# SCH_SimpleFOC-StepMini_2024-05-25.net
KiCad netlist of a schematic drawn in EasyEDA
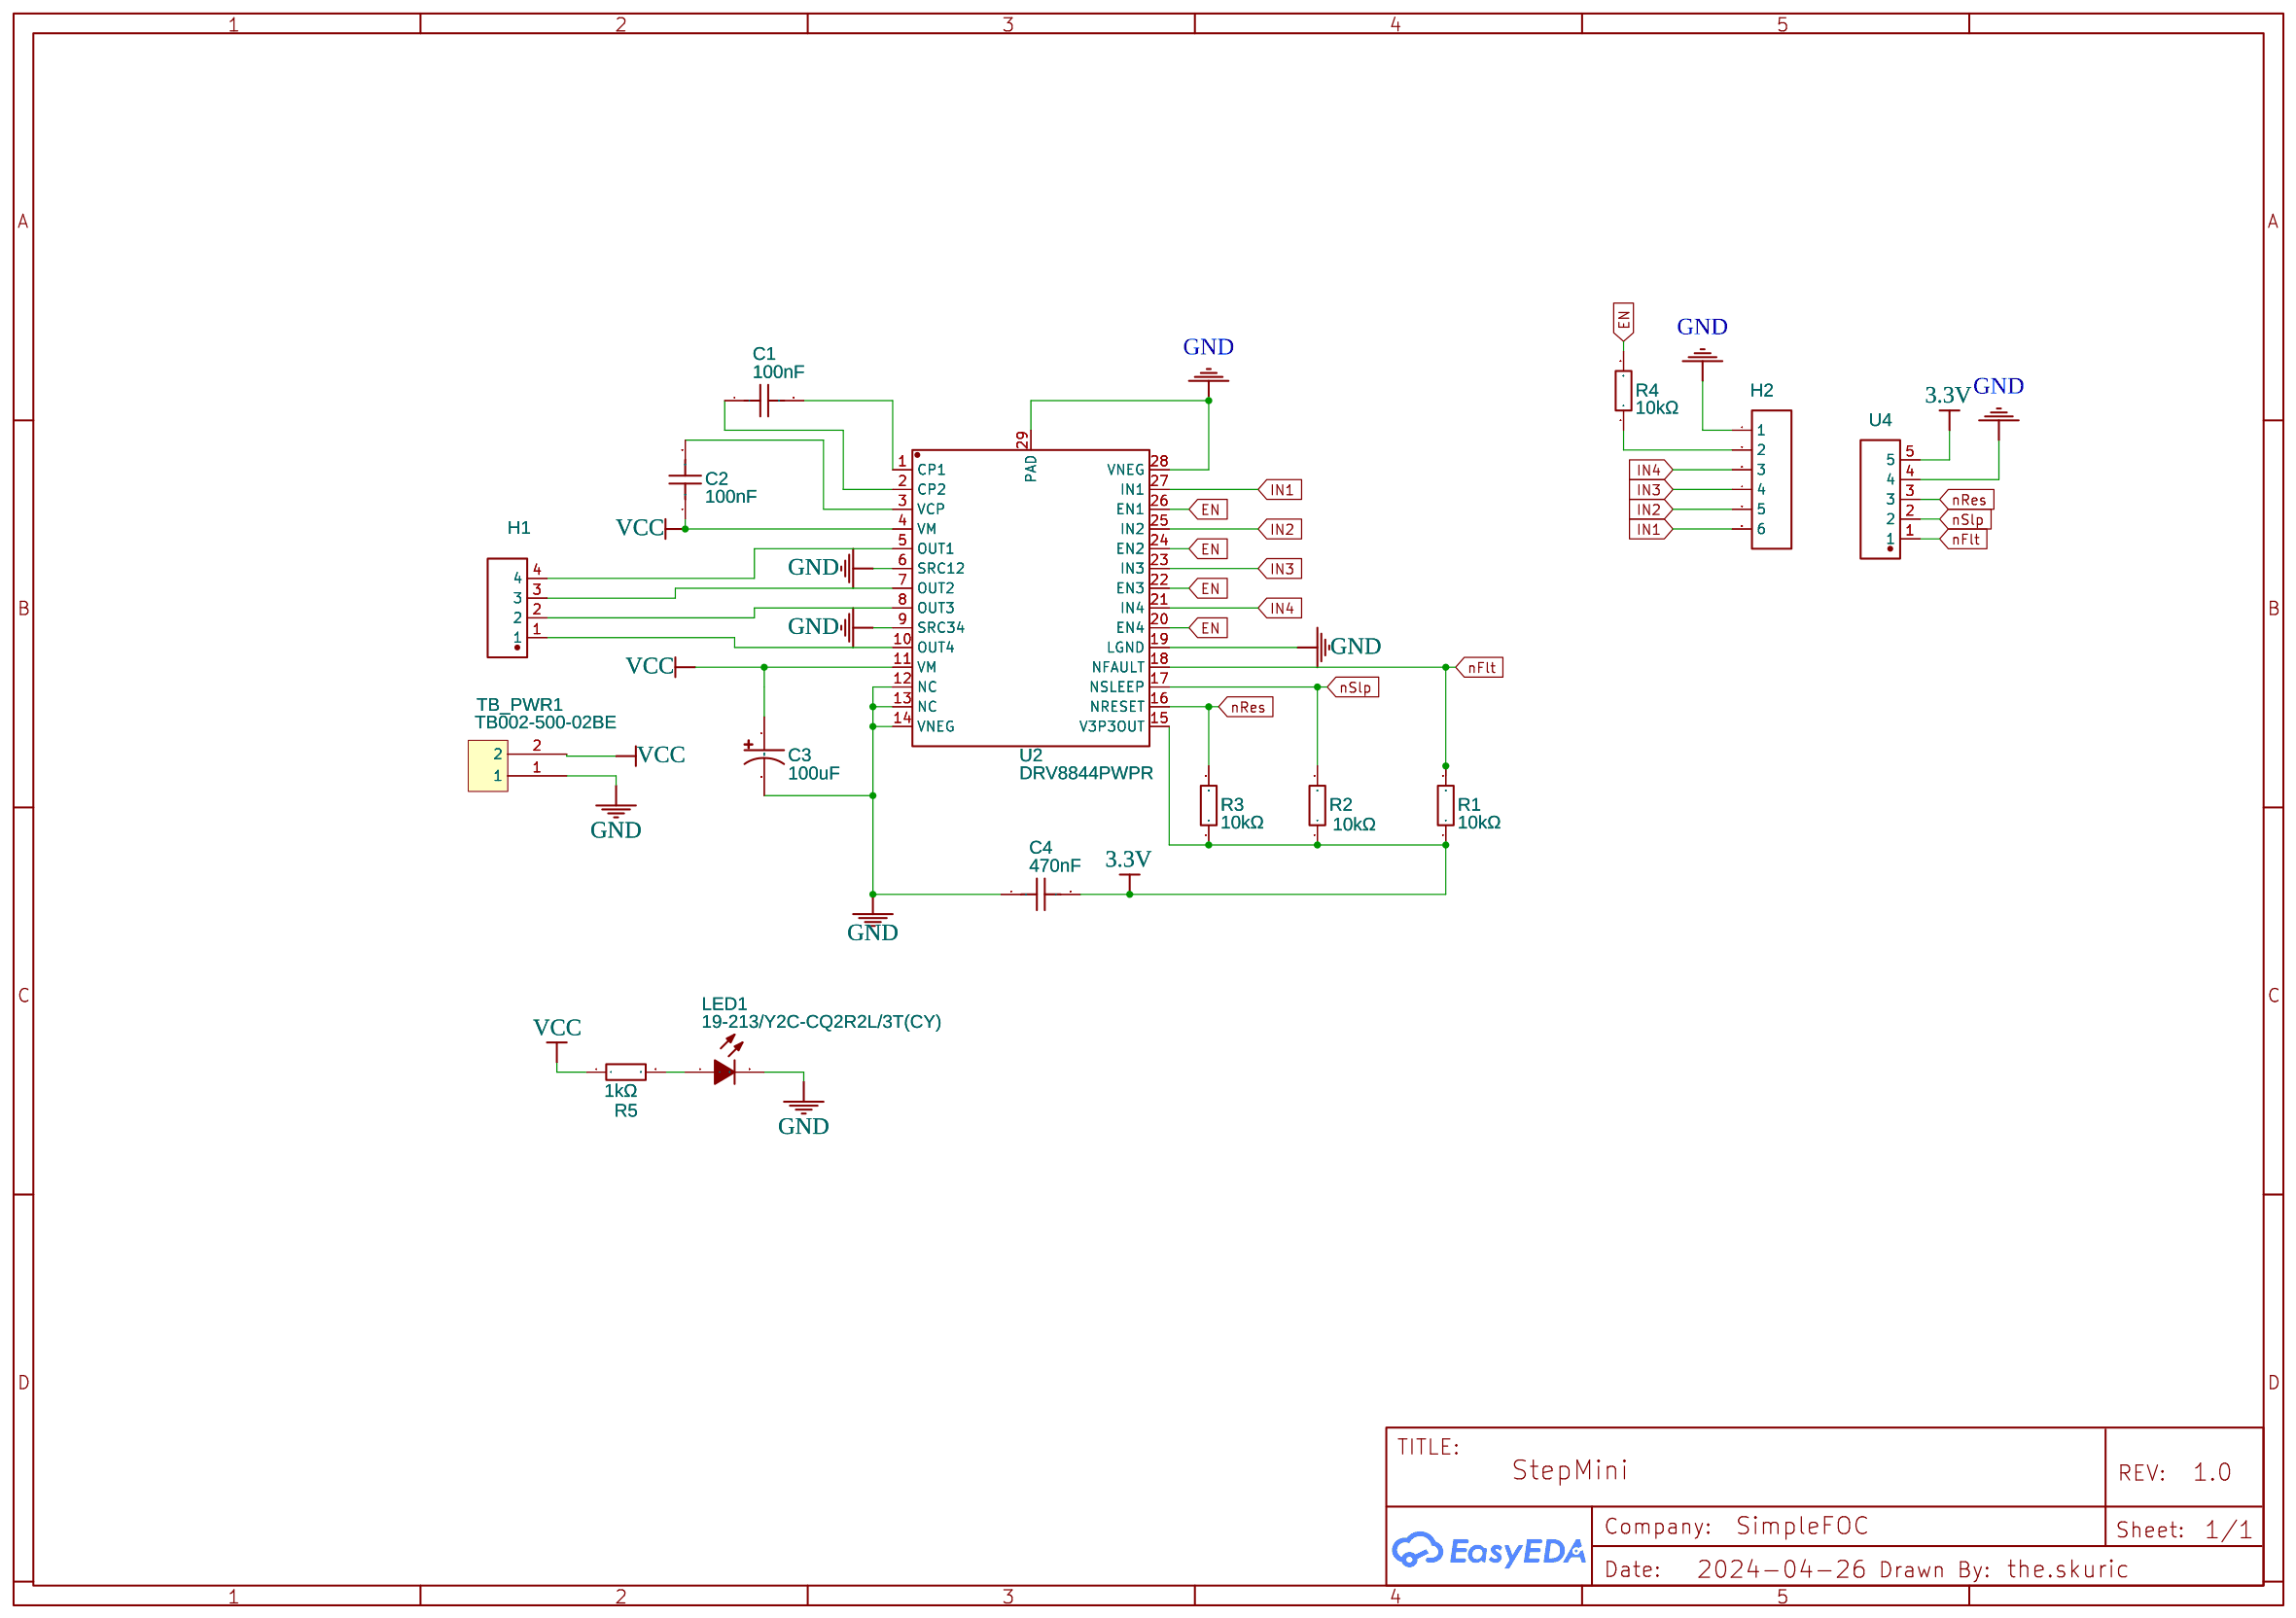
[diagram p0: schematic sheet]

(export (version "E")
  (design (tool "Eeschema 10.0.6"))
  (components
    (comp (ref "C1")
      (value "100nF")
      (fields (field (name "Manufacturer Part") "CL10B104KB8NNNC") (field (name "Manufacturer") "SAMSUNG"))
      (libsource (lib "") (part "CL10B104KB8NNNC_1"))
    )
    (comp (ref "C2")
      (value "100nF")
      (fields (field (name "Manufacturer Part") "CL10B104KB8NNNC") (field (name "Manufacturer") "SAMSUNG"))
      (libsource (lib "") (part "CL10B104KB8NNNC"))
    )
    (comp (ref "C3")
      (value "100uF")
      (fields
        (field (name "Manufacturer Part") "VT1V101M-CRE77")
        (field (name "Manufacturer") "Vertical Technology")
      )
      (libsource (lib "") (part "VT1V101M-CRE77"))
    )
    (comp (ref "C4")
      (value "470nF")
      (fields (field (name "Manufacturer Part") "CC0603ZRY5V6BB474") (field (name "Manufacturer") "YAGEO"))
      (libsource (lib "") (part "CC0603ZRY5V6BB474"))
    )
    (comp (ref "H1")
      (value "KH-2.54PH180-1X4P-L11.5")
      (fields (field (name "Manufacturer") "kinghelm(金航标)"))
      (libsource (lib "") (part "KH-2.54PH180-1X4P-L11.5"))
    )
    (comp (ref "H2")
      (value "Header-Male-2.54_1x6")
      (fields (field (name "Manufacturer Part") "2.54-1x6P直针") (field (name "Manufacturer") "BOOMELE(博穆精密)"))
      (libsource (lib "") (part "Header-Male-2.54_1x6"))
    )
    (comp (ref "LED1")
      (value "19-213/Y2C-CQ2R2L/3T(CY)")
      (fields (field (name "Manufacturer") "EVERLIGHT"))
      (libsource (lib "") (part "19-213/Y2C-CQ2R2L/3T(CY)"))
    )
    (comp (ref "R1")
      (value "10kΩ")
      (fields (field (name "Manufacturer Part") "0603WAF4701T5E") (field (name "Manufacturer") "UniOhm"))
      (libsource (lib "") (part "0603WAF4701T5E"))
    )
    (comp (ref "R2")
      (value "10kΩ")
      (fields (field (name "Manufacturer Part") "0603WAF4701T5E") (field (name "Manufacturer") "UniOhm"))
      (libsource (lib "") (part "0603WAF4701T5E"))
    )
    (comp (ref "R3")
      (value "10kΩ")
      (fields (field (name "Manufacturer Part") "0603WAF4701T5E") (field (name "Manufacturer") "UniOhm"))
      (libsource (lib "") (part "0603WAF4701T5E"))
    )
    (comp (ref "R4")
      (value "10kΩ")
      (fields (field (name "Manufacturer Part") "0603WAF4701T5E") (field (name "Manufacturer") "UniOhm"))
      (libsource (lib "") (part "0603WAF4701T5E"))
    )
    (comp (ref "R5")
      (value "1kΩ")
      (fields (field (name "Manufacturer Part") "0603WAF4701T5E") (field (name "Manufacturer") "UniOhm"))
      (libsource (lib "") (part "0603WAF4701T5E_1"))
    )
    (comp (ref "TB_PWR1") (value "TB002-500-02BE") (libsource (lib "") (part "TB002-500-02BE")))
    (comp (ref "U2")
      (value "DRV8844PWPR")
      (fields (field (name "Manufacturer") "TI(德州仪器)"))
      (libsource (lib "") (part "DRV8844PWPR"))
    )
    (comp (ref "U4")
      (value "KH-2.54FH-1X5P-H8.5")
      (fields (field (name "Manufacturer") "kinghelm(金航标)"))
      (libsource (lib "") (part "KH-2.54FH-1X5P-H8.5"))
    )
  )
  (nets
    (net (code "1") (name "3.3V") (class "Default")
      (node (ref "C4") (pin "2") (pinfunction "2_2") (pintype "unspecified"))
      (node (ref "R1") (pin "1") (pinfunction "1_1") (pintype "input"))
      (node (ref "R2") (pin "1") (pinfunction "1_1") (pintype "input"))
      (node (ref "R3") (pin "1") (pinfunction "1_1") (pintype "input"))
      (node (ref "U2") (pin "15") (pinfunction "V3P3OUT_15") (pintype "unspecified"))
      (node (ref "U4") (pin "5") (pinfunction "5_5") (pintype "unspecified"))
    )
    (net (code "2") (name "EN") (class "Default")
      (node (ref "R4") (pin "2") (pinfunction "2_2") (pintype "input"))
      (node (ref "U2") (pin "20") (pinfunction "EN4_20") (pintype "unspecified"))
      (node (ref "U2") (pin "22") (pinfunction "EN3_22") (pintype "unspecified"))
      (node (ref "U2") (pin "24") (pinfunction "EN2_24") (pintype "unspecified"))
      (node (ref "U2") (pin "26") (pinfunction "EN1_26") (pintype "unspecified"))
    )
    (net (code "3") (name "GND") (class "Default")
      (node (ref "C3") (pin "2") (pinfunction "2_2") (pintype "unspecified"))
      (node (ref "C4") (pin "1") (pinfunction "1_1") (pintype "unspecified"))
      (node (ref "H2") (pin "1") (pinfunction "1_1") (pintype "input"))
      (node (ref "LED1") (pin "2") (pinfunction "C_2") (pintype "input"))
      (node (ref "TB_PWR1") (pin "1") (pinfunction "1_1") (pintype "unspecified"))
      (node (ref "U2") (pin "12") (pinfunction "NC_12") (pintype "unspecified"))
      (node (ref "U2") (pin "13") (pinfunction "NC_13") (pintype "unspecified"))
      (node (ref "U2") (pin "14") (pinfunction "VNEG_14") (pintype "unspecified"))
      (node (ref "U2") (pin "19") (pinfunction "LGND_19") (pintype "unspecified"))
      (node (ref "U2") (pin "28") (pinfunction "VNEG_28") (pintype "unspecified"))
      (node (ref "U2") (pin "29") (pinfunction "PAD_29") (pintype "unspecified"))
      (node (ref "U2") (pin "6") (pinfunction "SRC12_6") (pintype "unspecified"))
      (node (ref "U2") (pin "9") (pinfunction "SRC34_9") (pintype "unspecified"))
      (node (ref "U4") (pin "4") (pinfunction "4_4") (pintype "unspecified"))
    )
    (net (code "4") (name "IN1") (class "Default")
      (node (ref "H2") (pin "6") (pinfunction "6_6") (pintype "input"))
      (node (ref "U2") (pin "27") (pinfunction "IN1_27") (pintype "unspecified"))
    )
    (net (code "5") (name "IN2") (class "Default")
      (node (ref "H2") (pin "5") (pinfunction "5_5") (pintype "input"))
      (node (ref "U2") (pin "25") (pinfunction "IN2_25") (pintype "unspecified"))
    )
    (net (code "6") (name "IN3") (class "Default")
      (node (ref "H2") (pin "4") (pinfunction "4_4") (pintype "input"))
      (node (ref "U2") (pin "23") (pinfunction "IN3_23") (pintype "unspecified"))
    )
    (net (code "7") (name "IN4") (class "Default")
      (node (ref "H2") (pin "3") (pinfunction "3_3") (pintype "input"))
      (node (ref "U2") (pin "21") (pinfunction "IN4_21") (pintype "unspecified"))
    )
    (net (code "8") (name "Net-(H2-Pad2)") (class "Default")
      (node (ref "H2") (pin "2") (pinfunction "2_2") (pintype "input"))
      (node (ref "R4") (pin "1") (pinfunction "1_1") (pintype "input"))
    )
    (net (code "9") (name "Net-(LED1-A)") (class "Default")
      (node (ref "LED1") (pin "1") (pinfunction "A_1") (pintype "input"))
      (node (ref "R5") (pin "2") (pinfunction "2_2") (pintype "input"))
    )
    (net (code "10") (name "Net-(U2-CP1)") (class "Default")
      (node (ref "C1") (pin "2") (pinfunction "2_2") (pintype "unspecified"))
      (node (ref "U2") (pin "1") (pinfunction "CP1_1") (pintype "unspecified"))
    )
    (net (code "11") (name "Net-(U2-CP2)") (class "Default")
      (node (ref "C1") (pin "1") (pinfunction "1_1") (pintype "unspecified"))
      (node (ref "U2") (pin "2") (pinfunction "CP2_2") (pintype "unspecified"))
    )
    (net (code "12") (name "Net-(U2-OUT1)") (class "Default")
      (node (ref "H1") (pin "4") (pinfunction "4_4") (pintype "unspecified"))
      (node (ref "U2") (pin "5") (pinfunction "OUT1_5") (pintype "unspecified"))
    )
    (net (code "13") (name "Net-(U2-OUT2)") (class "Default")
      (node (ref "H1") (pin "3") (pinfunction "3_3") (pintype "unspecified"))
      (node (ref "U2") (pin "7") (pinfunction "OUT2_7") (pintype "unspecified"))
    )
    (net (code "14") (name "Net-(U2-OUT3)") (class "Default")
      (node (ref "H1") (pin "2") (pinfunction "2_2") (pintype "unspecified"))
      (node (ref "U2") (pin "8") (pinfunction "OUT3_8") (pintype "unspecified"))
    )
    (net (code "15") (name "Net-(U2-OUT4)") (class "Default")
      (node (ref "H1") (pin "1") (pinfunction "1_1") (pintype "unspecified"))
      (node (ref "U2") (pin "10") (pinfunction "OUT4_10") (pintype "unspecified"))
    )
    (net (code "16") (name "Net-(U2-VCP)") (class "Default")
      (node (ref "C2") (pin "2") (pinfunction "2_2") (pintype "unspecified"))
      (node (ref "U2") (pin "3") (pinfunction "VCP_3") (pintype "unspecified"))
    )
    (net (code "17") (name "VCC") (class "Default")
      (node (ref "C2") (pin "1") (pinfunction "1_1") (pintype "unspecified"))
      (node (ref "C3") (pin "1") (pinfunction "1_1") (pintype "unspecified"))
      (node (ref "R5") (pin "1") (pinfunction "1_1") (pintype "input"))
      (node (ref "TB_PWR1") (pin "2") (pinfunction "2_2") (pintype "unspecified"))
      (node (ref "U2") (pin "11") (pinfunction "VM_11") (pintype "unspecified"))
      (node (ref "U2") (pin "4") (pinfunction "VM_4") (pintype "unspecified"))
    )
    (net (code "18") (name "nFlt") (class "Default")
      (node (ref "R1") (pin "2") (pinfunction "2_2") (pintype "input"))
      (node (ref "U2") (pin "18") (pinfunction "NFAULT_18") (pintype "unspecified"))
      (node (ref "U4") (pin "1") (pinfunction "1_1") (pintype "unspecified"))
    )
    (net (code "19") (name "nRes") (class "Default")
      (node (ref "R3") (pin "2") (pinfunction "2_2") (pintype "input"))
      (node (ref "U2") (pin "16") (pinfunction "NRESET_16") (pintype "unspecified"))
      (node (ref "U4") (pin "3") (pinfunction "3_3") (pintype "unspecified"))
    )
    (net (code "20") (name "nSlp") (class "Default")
      (node (ref "R2") (pin "2") (pinfunction "2_2") (pintype "input"))
      (node (ref "U2") (pin "17") (pinfunction "NSLEEP_17") (pintype "unspecified"))
      (node (ref "U4") (pin "2") (pinfunction "2_2") (pintype "unspecified"))
    )
  )
)
